# TEC_power2.net
KiCad netlist of a schematic drawn in Altium Designer
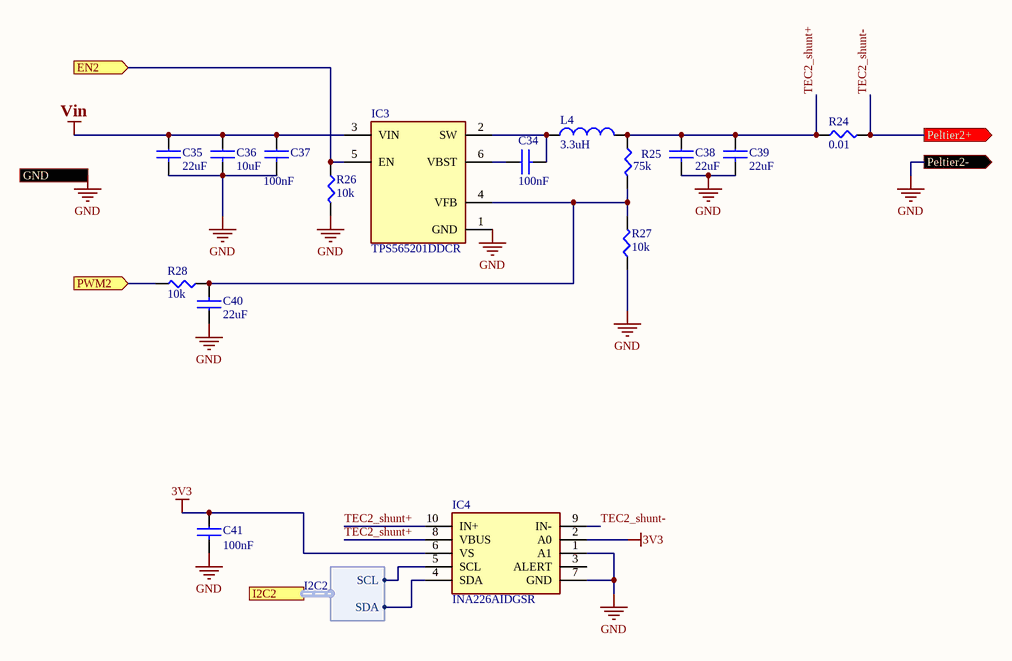
[diagram p0: TEC power2.SchDoc]

(export (version "E")
  (design (tool "Eeschema 10.0.6"))
  (components
    (comp (ref "C34")
      (value "100nF")
      (footprint "CAPC160X80X90L35N")
      (fields (field (name "LCSC PART #") "C14663") (field (name "PART NUMBER") "CC0603KRX7R9BB104"))
      (libsource (lib "Miscellaneous") (part "capacitor"))
    )
    (comp (ref "C35")
      (value "22uF")
      (footprint "CAPC200X125X110L50N")
      (fields (field (name "LCSC PART #") "C45783") (field (name "PART NUMBER") "CL21A226MAQNNNE"))
      (libsource (lib "Miscellaneous") (part "capacitor"))
    )
    (comp (ref "C36")
      (value "10uF")
      (footprint "CAPC200X125X110L50N")
      (fields (field (name "LCSC PART #") "C15850") (field (name "PART NUMBER") "CL21A106KAYNNNE"))
      (libsource (lib "Miscellaneous") (part "capacitor"))
    )
    (comp (ref "C37")
      (value "100nF")
      (footprint "CAPC160X80X90L35N")
      (fields (field (name "LCSC PART #") "C14663") (field (name "PART NUMBER") "CC0603KRX7R9BB104"))
      (libsource (lib "Miscellaneous") (part "capacitor"))
    )
    (comp (ref "C38")
      (value "22uF")
      (footprint "CAPC200X125X110L50N")
      (fields (field (name "LCSC PART #") "C45783") (field (name "PART NUMBER") "CL21A226MAQNNNE"))
      (libsource (lib "Miscellaneous") (part "capacitor"))
    )
    (comp (ref "C39")
      (value "22uF")
      (footprint "CAPC200X125X110L50N")
      (fields (field (name "LCSC PART #") "C45783") (field (name "PART NUMBER") "CL21A226MAQNNNE"))
      (libsource (lib "Miscellaneous") (part "capacitor"))
    )
    (comp (ref "C40")
      (value "22uF")
      (footprint "CAPC200X125X110L50N")
      (fields (field (name "LCSC PART #") "C45783") (field (name "PART NUMBER") "CL21A226MAQNNNE"))
      (libsource (lib "Miscellaneous") (part "capacitor"))
    )
    (comp (ref "C41")
      (value "100nF")
      (footprint "CAPC160X80X90L35N")
      (fields (field (name "LCSC PART #") "C14663") (field (name "PART NUMBER") "CC0603KRX7R9BB104"))
      (libsource (lib "Miscellaneous") (part "capacitor"))
    )
    (comp (ref "IC3")
      (value "TPS565201DDCR")
      (footprint "SOT95P280X110-6N")
      (description "Integrated Circuit")
      (libsource (lib "Miscellaneous") (part "TPS565201DDCR"))
    )
    (comp (ref "IC4")
      (value "INA226AIDGSR")
      (footprint "SOP10P50_300X490X110L55X22N")
      (description "Integrated Circuit")
      (fields (field (name "MOUSER2 PART NUMBER") "595-INA226AIDGSR") (field (name "LCSC PART #") "C49851"))
      (libsource (lib "Miscellaneous") (part "INA226AIDGSR"))
    )
    (comp (ref "L4")
      (value "3.3uH")
      (footprint "INDM730X660X300L160X290N")
      (description "Inductor")
      (fields (field (name "LCSC PART #") "C280586") (field (name "PART NUMBER") "MHCI06030-3R3M-R8A"))
      (libsource (lib "Miscellaneous") (part "Inductor"))
    )
    (comp (ref "R24")
      (value "0.01")
      (footprint "RESC200X125X70L40N")
      (fields (field (name "PART NUMBER") "1206W4F100MT5E") (field (name "LCSC PART #") "C127689"))
      (libsource (lib "Miscellaneous") (part "Resistor"))
    )
    (comp (ref "R25")
      (value "75k")
      (footprint "RESC160X80X90L30N")
      (fields (field (name "PART NUMBER") "0603WAF7502T5E") (field (name "LCSC PART #") "C46216"))
      (libsource (lib "Miscellaneous") (part "Resistor"))
    )
    (comp (ref "R26")
      (value "10k")
      (footprint "RESC160X80X90L30N")
      (fields (field (name "PART NUMBER") "0603WAF1002T5E") (field (name "LCSC PART #") "C25804"))
      (libsource (lib "Miscellaneous") (part "Resistor"))
    )
    (comp (ref "R27")
      (value "10k")
      (footprint "RESC160X80X90L30N")
      (fields (field (name "PART NUMBER") "0603WAF1002T5E") (field (name "LCSC PART #") "C25804"))
      (libsource (lib "Miscellaneous") (part "Resistor"))
    )
    (comp (ref "R28")
      (value "10k")
      (footprint "RESC160X80X90L30N")
      (fields (field (name "PART NUMBER") "0603WAF1002T5E") (field (name "LCSC PART #") "C25804"))
      (libsource (lib "Miscellaneous") (part "Resistor"))
    )
  )
  (nets
    (net (code "2") (name "/EN2") (class "Default")
      (node (ref "IC3") (pin "5") (pinfunction "EN_5") (pintype "passive"))
      (node (ref "R26") (pin "1") (pinfunction "1_1") (pintype "passive"))
    )
    (net (code "3") (name "/PWM2") (class "Default")
      (node (ref "R28") (pin "2") (pinfunction "2_2") (pintype "passive"))
    )
    (net (code "4") (name "/SCL") (class "Default")
      (node (ref "IC4") (pin "5") (pinfunction "SCL_5") (pintype "passive"))
    )
    (net (code "5") (name "/SDA") (class "Default")
      (node (ref "IC4") (pin "4") (pinfunction "SDA_4") (pintype "passive"))
    )
    (net (code "6") (name "/TEC2_shunt+") (class "Default")
      (node (ref "C38") (pin "1") (pinfunction "1_1") (pintype "passive"))
      (node (ref "C39") (pin "1") (pinfunction "1_1") (pintype "passive"))
      (node (ref "IC4") (pin "10") (pinfunction "IN+_10") (pintype "passive"))
      (node (ref "IC4") (pin "8") (pinfunction "VBUS_8") (pintype "passive"))
      (node (ref "L4") (pin "2") (pinfunction "2_2") (pintype "passive"))
      (node (ref "R24") (pin "1") (pinfunction "1_1") (pintype "passive"))
      (node (ref "R25") (pin "1") (pinfunction "1_1") (pintype "passive"))
    )
    (net (code "7") (name "/TEC2_shunt-") (class "Default")
      (node (ref "IC4") (pin "9") (pinfunction "IN-_9") (pintype "passive"))
      (node (ref "R24") (pin "2") (pinfunction "2_2") (pintype "passive"))
    )
    (net (code "9") (name "3V3") (class "Default")
      (node (ref "C41") (pin "1") (pinfunction "1_1") (pintype "passive"))
      (node (ref "IC4") (pin "2") (pinfunction "A0_2") (pintype "passive"))
      (node (ref "IC4") (pin "6") (pinfunction "VS_6") (pintype "passive"))
    )
    (net (code "10") (name "GND") (class "Default")
      (node (ref "C35") (pin "2") (pinfunction "2_2") (pintype "passive"))
      (node (ref "C36") (pin "2") (pinfunction "2_2") (pintype "passive"))
      (node (ref "C37") (pin "2") (pinfunction "2_2") (pintype "passive"))
      (node (ref "C38") (pin "2") (pinfunction "2_2") (pintype "passive"))
      (node (ref "C39") (pin "2") (pinfunction "2_2") (pintype "passive"))
      (node (ref "C40") (pin "1") (pinfunction "1_1") (pintype "passive"))
      (node (ref "C41") (pin "2") (pinfunction "2_2") (pintype "passive"))
      (node (ref "IC3") (pin "1") (pinfunction "GND_1") (pintype "passive"))
      (node (ref "IC4") (pin "1") (pinfunction "A1_1") (pintype "passive"))
      (node (ref "IC4") (pin "7") (pinfunction "GND_7") (pintype "passive"))
      (node (ref "R26") (pin "2") (pinfunction "2_2") (pintype "passive"))
      (node (ref "R27") (pin "1") (pinfunction "1_1") (pintype "passive"))
    )
    (net (code "11") (name "Net-(IC3-SW)") (class "Default")
      (node (ref "C34") (pin "2") (pinfunction "2_2") (pintype "passive"))
      (node (ref "IC3") (pin "2") (pinfunction "SW_2") (pintype "passive"))
      (node (ref "L4") (pin "1") (pinfunction "1_1") (pintype "passive"))
    )
    (net (code "12") (name "Net-(IC3-VBST)") (class "Default")
      (node (ref "C34") (pin "1") (pinfunction "1_1") (pintype "passive"))
      (node (ref "IC3") (pin "6") (pinfunction "VBST_6") (pintype "passive"))
    )
    (net (code "13") (name "Net-(IC3-VFB)") (class "Default")
      (node (ref "C40") (pin "2") (pinfunction "2_2") (pintype "passive"))
      (node (ref "IC3") (pin "4") (pinfunction "VFB_4") (pintype "passive"))
      (node (ref "R25") (pin "2") (pinfunction "2_2") (pintype "passive"))
      (node (ref "R27") (pin "2") (pinfunction "2_2") (pintype "passive"))
      (node (ref "R28") (pin "1") (pinfunction "1_1") (pintype "passive"))
    )
    (net (code "14") (name "Vin") (class "Default")
      (node (ref "C35") (pin "1") (pinfunction "1_1") (pintype "passive"))
      (node (ref "C36") (pin "1") (pinfunction "1_1") (pintype "passive"))
      (node (ref "C37") (pin "1") (pinfunction "1_1") (pintype "passive"))
      (node (ref "IC3") (pin "3") (pinfunction "VIN_3") (pintype "passive"))
    )
    (net (code "15") (name "unconnected-(IC4-ALERT-Pad3)") (class "Default")
      (node (ref "IC4") (pin "3") (pinfunction "ALERT_3") (pintype "passive"))
    )
  )
)
